# Suntracker_v1_2.net
KiCad netlist of a schematic drawn in EAGLE
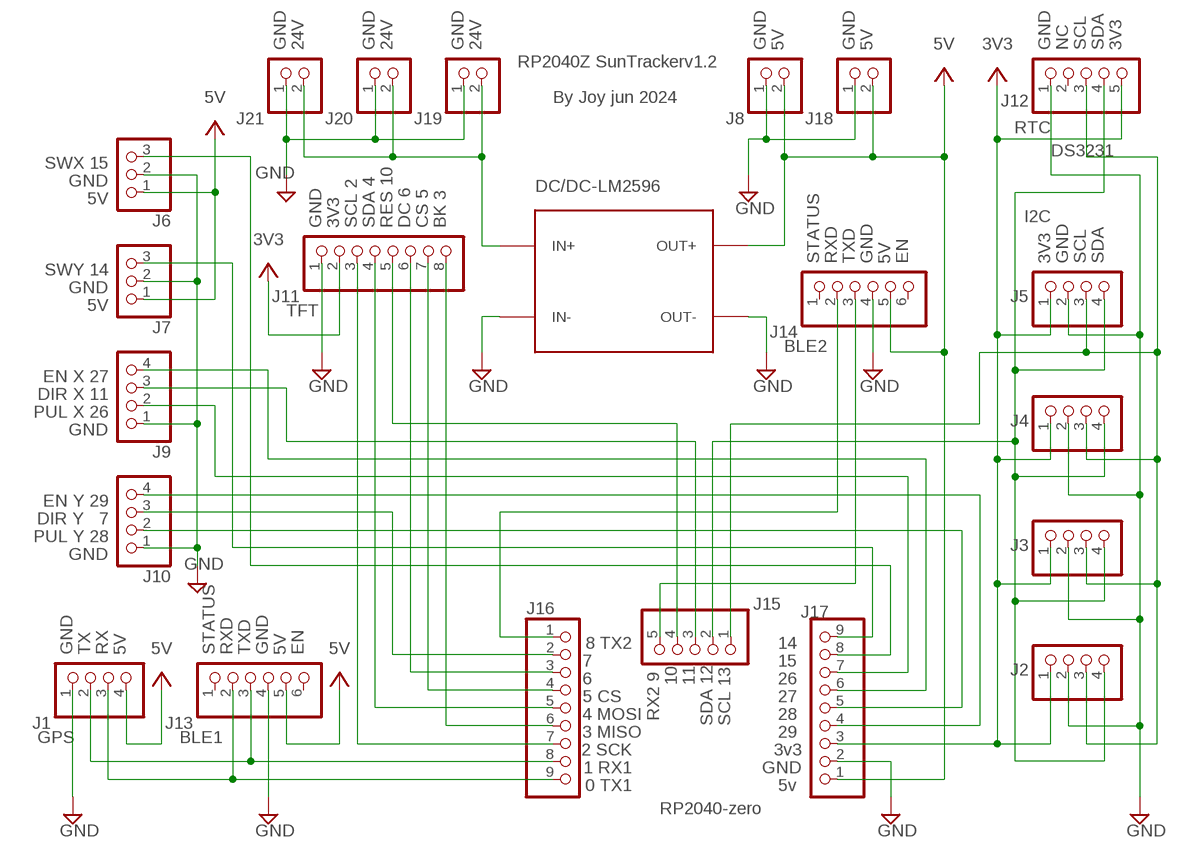
[diagram p0: schematic, sheet 1]

(export (version "E")
  (design (tool "Eeschema 10.0.6"))
  (components
    (comp (ref "J1")
      (value "PINHD-1X04_2.54")
      (footprint "eagle-import:1X04")
      (libsource (lib "eagle-import") (part "PINHD-1X04_2.54"))
    )
    (comp (ref "J2")
      (value "PINHD-1X04_2.54")
      (footprint "eagle-import:1X04")
      (libsource (lib "eagle-import") (part "PINHD-1X04_2.54"))
    )
    (comp (ref "J3")
      (value "PINHD-1X04_2.54")
      (footprint "eagle-import:1X04")
      (libsource (lib "eagle-import") (part "PINHD-1X04_2.54"))
    )
    (comp (ref "J4")
      (value "PINHD-1X04_2.54")
      (footprint "eagle-import:1X04")
      (libsource (lib "eagle-import") (part "PINHD-1X04_2.54"))
    )
    (comp (ref "J5")
      (value "PINHD-1X04_2.54")
      (footprint "eagle-import:1X04")
      (libsource (lib "eagle-import") (part "PINHD-1X04_2.54"))
    )
    (comp (ref "J6")
      (value "PINHD-1X3")
      (footprint "eagle-import:1X03")
      (libsource (lib "eagle-import") (part "PINHD-1X3"))
    )
    (comp (ref "J7")
      (value "PINHD-1X3")
      (footprint "eagle-import:1X03")
      (libsource (lib "eagle-import") (part "PINHD-1X3"))
    )
    (comp (ref "J8")
      (value "PINHD-1X2")
      (footprint "eagle-import:1X02")
      (libsource (lib "eagle-import") (part "PINHD-1X2"))
    )
    (comp (ref "J9")
      (value "PINHD-1X04_2.54")
      (footprint "eagle-import:1X04")
      (libsource (lib "eagle-import") (part "PINHD-1X04_2.54"))
    )
    (comp (ref "J10")
      (value "PINHD-1X04_2.54")
      (footprint "eagle-import:1X04")
      (libsource (lib "eagle-import") (part "PINHD-1X04_2.54"))
    )
    (comp (ref "J11")
      (value "PINHD-1X8")
      (footprint "eagle-import:1X08")
      (libsource (lib "eagle-import") (part "PINHD-1X8"))
    )
    (comp (ref "J12")
      (value "PINHD-1X05_2.54")
      (footprint "eagle-import:1X05")
      (libsource (lib "eagle-import") (part "PINHD-1X05_2.54"))
    )
    (comp (ref "J13")
      (value "PINHD-1X06_2.54")
      (footprint "eagle-import:1X06")
      (libsource (lib "eagle-import") (part "PINHD-1X06_2.54"))
    )
    (comp (ref "J14")
      (value "PINHD-1X06_2.54")
      (footprint "eagle-import:1X06")
      (libsource (lib "eagle-import") (part "PINHD-1X06_2.54"))
    )
    (comp (ref "J15")
      (value "PINHD-1X05_2.54")
      (footprint "eagle-import:1X05")
      (libsource (lib "eagle-import") (part "PINHD-1X05_2.54"))
    )
    (comp (ref "J16")
      (value "PINHD-1X9/90")
      (footprint "eagle-import:1X09_90")
      (libsource (lib "eagle-import") (part "PINHD-1X9/90"))
    )
    (comp (ref "J17")
      (value "PINHD-1X9/90")
      (footprint "eagle-import:1X09_90")
      (libsource (lib "eagle-import") (part "PINHD-1X9/90"))
    )
    (comp (ref "J18")
      (value "PINHD-1X2")
      (footprint "eagle-import:1X02")
      (libsource (lib "eagle-import") (part "PINHD-1X2"))
    )
    (comp (ref "J19")
      (value "PINHD-1X2")
      (footprint "eagle-import:1X02")
      (libsource (lib "eagle-import") (part "PINHD-1X2"))
    )
    (comp (ref "J20")
      (value "PINHD-1X2")
      (footprint "eagle-import:1X02")
      (libsource (lib "eagle-import") (part "PINHD-1X2"))
    )
    (comp (ref "J21")
      (value "PINHD-1X2")
      (footprint "eagle-import:1X02")
      (libsource (lib "eagle-import") (part "PINHD-1X2"))
    )
    (comp (ref "U1")
      (value "DC/DC-LM2596")
      (footprint "eagle-import:DC-DC-STEP-DOWN-LM2596")
      (libsource (lib "eagle-import") (part "DC-DC-STEP-DOWN-LM2596"))
    )
  )
  (nets
    (net (code "1") (name "GND") (class "Default")
      (node (ref "J1") (pin "1") (pinfunction "1_1") (pintype "passive"))
      (node (ref "J10") (pin "1") (pinfunction "1_1") (pintype "passive"))
      (node (ref "J11") (pin "1") (pinfunction "1_1") (pintype "passive"))
      (node (ref "J12") (pin "1") (pinfunction "1_1") (pintype "passive"))
      (node (ref "J13") (pin "4") (pinfunction "4_4") (pintype "passive"))
      (node (ref "J14") (pin "4") (pinfunction "4_4") (pintype "passive"))
      (node (ref "J17") (pin "2") (pinfunction "2_2") (pintype "passive"))
      (node (ref "J18") (pin "1") (pinfunction "1_1") (pintype "passive"))
      (node (ref "J19") (pin "1") (pinfunction "1_1") (pintype "passive"))
      (node (ref "J2") (pin "2") (pinfunction "2_2") (pintype "passive"))
      (node (ref "J20") (pin "1") (pinfunction "1_1") (pintype "passive"))
      (node (ref "J21") (pin "1") (pinfunction "1_1") (pintype "passive"))
      (node (ref "J3") (pin "2") (pinfunction "2_2") (pintype "passive"))
      (node (ref "J4") (pin "2") (pinfunction "2_2") (pintype "passive"))
      (node (ref "J5") (pin "2") (pinfunction "2_2") (pintype "passive"))
      (node (ref "J6") (pin "2") (pinfunction "2_2") (pintype "passive"))
      (node (ref "J7") (pin "2") (pinfunction "2_2") (pintype "passive"))
      (node (ref "J8") (pin "1") (pinfunction "1_1") (pintype "passive"))
      (node (ref "J9") (pin "1") (pinfunction "1_1") (pintype "passive"))
      (node (ref "U1") (pin "IN-") (pinfunction "IN-_IN-") (pintype "bidirectional"))
      (node (ref "U1") (pin "OUT-") (pinfunction "OUT-_OUT-") (pintype "bidirectional"))
    )
    (net (code "2") (name "Net-(J1-Pad2)") (class "Default")
      (node (ref "J1") (pin "2") (pinfunction "2_2") (pintype "passive"))
      (node (ref "J13") (pin "3") (pinfunction "3_3") (pintype "passive"))
      (node (ref "J16") (pin "8") (pinfunction "8_8") (pintype "passive"))
    )
    (net (code "3") (name "Net-(J1-Pad3)") (class "Default")
      (node (ref "J1") (pin "3") (pinfunction "3_3") (pintype "passive"))
      (node (ref "J13") (pin "2") (pinfunction "2_2") (pintype "passive"))
      (node (ref "J16") (pin "9") (pinfunction "9_9") (pintype "passive"))
    )
    (net (code "4") (name "Net-(J10-Pad2)") (class "Default")
      (node (ref "J10") (pin "2") (pinfunction "2_2") (pintype "passive"))
      (node (ref "J17") (pin "5") (pinfunction "5_5") (pintype "passive"))
    )
    (net (code "5") (name "Net-(J10-Pad3)") (class "Default")
      (node (ref "J10") (pin "3") (pinfunction "3_3") (pintype "passive"))
      (node (ref "J16") (pin "2") (pinfunction "2_2") (pintype "passive"))
    )
    (net (code "6") (name "Net-(J10-Pad4)") (class "Default")
      (node (ref "J10") (pin "4") (pinfunction "4_4") (pintype "passive"))
      (node (ref "J17") (pin "4") (pinfunction "4_4") (pintype "passive"))
    )
    (net (code "7") (name "Net-(J11-Pad3)") (class "Default")
      (node (ref "J11") (pin "3") (pinfunction "3_3") (pintype "passive"))
      (node (ref "J16") (pin "7") (pinfunction "7_7") (pintype "passive"))
    )
    (net (code "8") (name "Net-(J11-Pad4)") (class "Default")
      (node (ref "J11") (pin "4") (pinfunction "4_4") (pintype "passive"))
      (node (ref "J16") (pin "5") (pinfunction "5_5") (pintype "passive"))
    )
    (net (code "9") (name "Net-(J11-Pad5)") (class "Default")
      (node (ref "J11") (pin "5") (pinfunction "5_5") (pintype "passive"))
      (node (ref "J15") (pin "4") (pinfunction "4_4") (pintype "passive"))
    )
    (net (code "10") (name "Net-(J11-Pad6)") (class "Default")
      (node (ref "J11") (pin "6") (pinfunction "6_6") (pintype "passive"))
      (node (ref "J16") (pin "3") (pinfunction "3_3") (pintype "passive"))
    )
    (net (code "11") (name "Net-(J11-Pad7)") (class "Default")
      (node (ref "J11") (pin "7") (pinfunction "7_7") (pintype "passive"))
      (node (ref "J16") (pin "4") (pinfunction "4_4") (pintype "passive"))
    )
    (net (code "12") (name "Net-(J11-Pad8)") (class "Default")
      (node (ref "J11") (pin "8") (pinfunction "8_8") (pintype "passive"))
      (node (ref "J16") (pin "6") (pinfunction "6_6") (pintype "passive"))
    )
    (net (code "13") (name "Net-(J12-Pad3)") (class "Default")
      (node (ref "J12") (pin "3") (pinfunction "3_3") (pintype "passive"))
      (node (ref "J15") (pin "1") (pinfunction "1_1") (pintype "passive"))
      (node (ref "J2") (pin "3") (pinfunction "3_3") (pintype "passive"))
      (node (ref "J3") (pin "3") (pinfunction "3_3") (pintype "passive"))
      (node (ref "J4") (pin "3") (pinfunction "3_3") (pintype "passive"))
      (node (ref "J5") (pin "3") (pinfunction "3_3") (pintype "passive"))
    )
    (net (code "14") (name "Net-(J12-Pad4)") (class "Default")
      (node (ref "J12") (pin "4") (pinfunction "4_4") (pintype "passive"))
      (node (ref "J15") (pin "2") (pinfunction "2_2") (pintype "passive"))
      (node (ref "J2") (pin "4") (pinfunction "4_4") (pintype "passive"))
      (node (ref "J3") (pin "4") (pinfunction "4_4") (pintype "passive"))
      (node (ref "J4") (pin "4") (pinfunction "4_4") (pintype "passive"))
      (node (ref "J5") (pin "4") (pinfunction "4_4") (pintype "passive"))
    )
    (net (code "15") (name "Net-(J14-Pad2)") (class "Default")
      (node (ref "J14") (pin "2") (pinfunction "2_2") (pintype "passive"))
      (node (ref "J16") (pin "1") (pinfunction "1_1") (pintype "passive"))
    )
    (net (code "16") (name "Net-(J14-Pad3)") (class "Default")
      (node (ref "J14") (pin "3") (pinfunction "3_3") (pintype "passive"))
      (node (ref "J15") (pin "5") (pinfunction "5_5") (pintype "passive"))
    )
    (net (code "17") (name "Net-(J15-Pad3)") (class "Default")
      (node (ref "J15") (pin "3") (pinfunction "3_3") (pintype "passive"))
      (node (ref "J9") (pin "3") (pinfunction "3_3") (pintype "passive"))
    )
    (net (code "18") (name "Net-(J17-Pad6)") (class "Default")
      (node (ref "J17") (pin "6") (pinfunction "6_6") (pintype "passive"))
      (node (ref "J9") (pin "4") (pinfunction "4_4") (pintype "passive"))
    )
    (net (code "19") (name "Net-(J17-Pad7)") (class "Default")
      (node (ref "J17") (pin "7") (pinfunction "7_7") (pintype "passive"))
      (node (ref "J9") (pin "2") (pinfunction "2_2") (pintype "passive"))
    )
    (net (code "20") (name "Net-(J17-Pad8)") (class "Default")
      (node (ref "J17") (pin "8") (pinfunction "8_8") (pintype "passive"))
      (node (ref "J6") (pin "3") (pinfunction "3_3") (pintype "passive"))
    )
    (net (code "21") (name "Net-(J17-Pad9)") (class "Default")
      (node (ref "J17") (pin "9") (pinfunction "9_9") (pintype "passive"))
      (node (ref "J7") (pin "3") (pinfunction "3_3") (pintype "passive"))
    )
    (net (code "22") (name "Net-(J19-Pad2)") (class "Default")
      (node (ref "J19") (pin "2") (pinfunction "2_2") (pintype "passive"))
      (node (ref "J20") (pin "2") (pinfunction "2_2") (pintype "passive"))
      (node (ref "J21") (pin "2") (pinfunction "2_2") (pintype "passive"))
      (node (ref "U1") (pin "IN+") (pinfunction "IN+_IN+") (pintype "bidirectional"))
    )
    (net (code "23") (name "V+") (class "Default")
      (node (ref "J1") (pin "4") (pinfunction "4_4") (pintype "passive"))
      (node (ref "J11") (pin "2") (pinfunction "2_2") (pintype "passive"))
      (node (ref "J12") (pin "5") (pinfunction "5_5") (pintype "passive"))
      (node (ref "J13") (pin "5") (pinfunction "5_5") (pintype "passive"))
      (node (ref "J14") (pin "5") (pinfunction "5_5") (pintype "passive"))
      (node (ref "J17") (pin "1") (pinfunction "1_1") (pintype "passive"))
      (node (ref "J17") (pin "3") (pinfunction "3_3") (pintype "passive"))
      (node (ref "J18") (pin "2") (pinfunction "2_2") (pintype "passive"))
      (node (ref "J2") (pin "1") (pinfunction "1_1") (pintype "passive"))
      (node (ref "J3") (pin "1") (pinfunction "1_1") (pintype "passive"))
      (node (ref "J4") (pin "1") (pinfunction "1_1") (pintype "passive"))
      (node (ref "J5") (pin "1") (pinfunction "1_1") (pintype "passive"))
      (node (ref "J6") (pin "1") (pinfunction "1_1") (pintype "passive"))
      (node (ref "J7") (pin "1") (pinfunction "1_1") (pintype "passive"))
      (node (ref "J8") (pin "2") (pinfunction "2_2") (pintype "passive"))
      (node (ref "U1") (pin "OUT+") (pinfunction "OUT+_OUT+") (pintype "bidirectional"))
    )
    (net (code "24") (name "unconnected-(J12-Pad2)") (class "Default")
      (node (ref "J12") (pin "2") (pinfunction "2_2") (pintype "passive"))
    )
    (net (code "25") (name "unconnected-(J13-Pad1)") (class "Default")
      (node (ref "J13") (pin "1") (pinfunction "1_1") (pintype "passive"))
    )
    (net (code "26") (name "unconnected-(J13-Pad6)") (class "Default")
      (node (ref "J13") (pin "6") (pinfunction "6_6") (pintype "passive"))
    )
    (net (code "27") (name "unconnected-(J14-Pad1)") (class "Default")
      (node (ref "J14") (pin "1") (pinfunction "1_1") (pintype "passive"))
    )
    (net (code "28") (name "unconnected-(J14-Pad6)") (class "Default")
      (node (ref "J14") (pin "6") (pinfunction "6_6") (pintype "passive"))
    )
  )
)
